# USB_Connector.net
KiCad netlist of a schematic drawn in Altium Designer
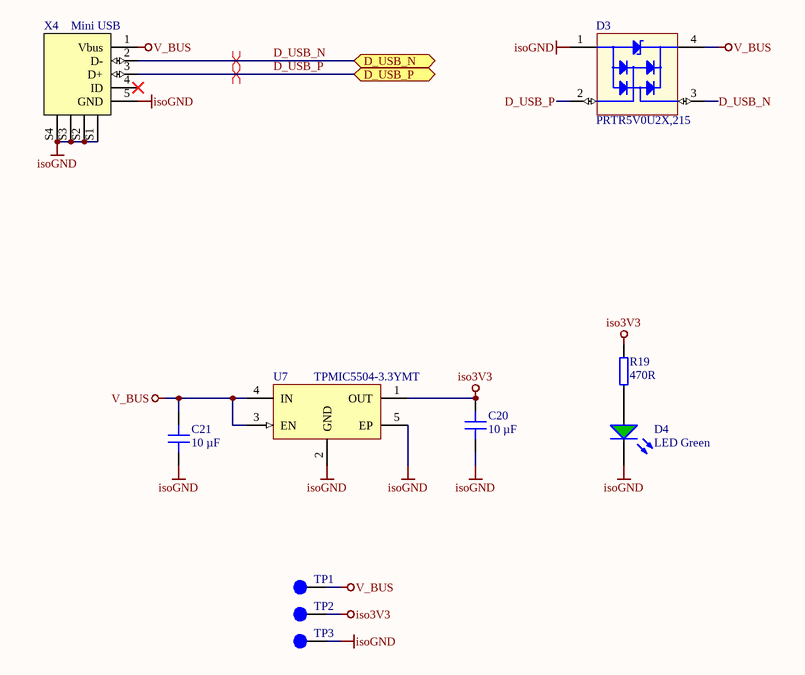
[diagram p0: USB_Connector.SchDoc]

(export (version "E")
  (design (tool "Eeschema 10.0.6"))
  (components
    (comp (ref "C20")
      (value "10 µF")
      (footprint "C_0603")
      (description "Capacitor 0603, 16 VDC, 10 µF, X5R")
      (fields
        (field (name "MANUFACTURER PART NUMBER") "CL10A106MO8NQNC")
        (field (name "MANUFACTURER") "Samsung Electro-Mechanics")
        (field (name "CREATED FROM") "AGeiger")
      )
      (libsource (lib "user") (part "Capacitor"))
    )
    (comp (ref "C21")
      (value "10 µF")
      (footprint "C_0603")
      (description "Capacitor 0603, 16 VDC, 10 µF, X5R")
      (fields
        (field (name "MANUFACTURER PART NUMBER") "CL10A106MO8NQNC")
        (field (name "MANUFACTURER") "Samsung Electro-Mechanics")
        (field (name "CREATED FROM") "AGeiger")
      )
      (libsource (lib "user") (part "Capacitor"))
    )
    (comp (ref "D3")
      (value "PRTR5V0U2X,215")
      (footprint "SOT-143B-4")
      (description "ESD Suppressors / TVS Diodes PRTR5V0U2X/SOT143/SOT4")
      (fields
        (field (name "MANUFACTURER") "Nexperia")
        (field (name "LCSC PART NUMBER") "C12333")
        (field (name "CREATED FROM") "AGeiger")
      )
      (libsource (lib "user") (part "CD143A-SRxx"))
    )
    (comp (ref "D4")
      (value "LED Green")
      (footprint "WL-SMCW_0603")
      (description "LED GREEN 520~535NM 112~258MCD@20MA TOP VIEW 0603 ROHS")
      (fields
        (field (name "MANUFACTURER PART NUMBER") "19-217/GHC-YR1S2/3T")
        (field (name "MANUFACTURER") "Everlight Elec")
        (field (name "CREATED FROM") "T. Wendt")
      )
      (libsource (lib "user") (part "LED_Green"))
    )
    (comp (ref "R19")
      (value "470R")
      (footprint "RES 0603_1608")
      (description "SMD resistor E24 series")
      (fields
        (field (name "MANUFACTURER PART NUMBER") "RK73B1JTTD471J")
        (field (name "MANUFACTURER") "KOA Speer")
        (field (name "CREATED FROM") "MGremer")
      )
      (libsource (lib "user") (part "Resistor"))
    )
    (comp (ref "TP1")
      (value "Testpoint 1mm")
      (footprint "TP_1mm")
      (fields
        (field (name "MANUFACTURER PART NUMBER") "NULL")
        (field (name "CREATED") "2018_06_25_AGeiger")
        (field (name "CREATED FROM") "AGeiger")
      )
      (libsource (lib "user") (part "TP_1mm"))
    )
    (comp (ref "TP2")
      (value "Testpoint 1mm")
      (footprint "TP_1mm")
      (fields
        (field (name "MANUFACTURER PART NUMBER") "NULL")
        (field (name "CREATED") "2018_06_25_AGeiger")
        (field (name "CREATED FROM") "AGeiger")
      )
      (libsource (lib "user") (part "TP_1mm"))
    )
    (comp (ref "TP3")
      (value "Testpoint 1mm")
      (footprint "TP_1mm")
      (fields
        (field (name "MANUFACTURER PART NUMBER") "NULL")
        (field (name "CREATED") "2018_06_25_AGeiger")
        (field (name "CREATED FROM") "AGeiger")
      )
      (libsource (lib "user") (part "TP_1mm"))
    )
    (comp (ref "U7")
      (value "TPMIC5504-3.3YMT")
      (footprint "DFN-4-EP")
      (description "DFN-4-EP(1x1) Linear Voltage Regulators (LDO) ROHS")
      (fields
        (field (name "MANUFACTURER") "TECH PUBLIC")
        (field (name "LCSC PART NUMBER") "C3021135")
        (field (name "CREATED FROM") "AGeiger")
      )
      (libsource (lib "user") (part "TPMIC5504-3.3YMT"))
    )
    (comp (ref "X4")
      (value "Mini USB")
      (footprint "MINI_USB_5S_B _TYPE")
      (description "1A 1 Surface Mount 5P Female -30℃~+80℃ SMD USB Connectors ROHS")
      (fields
        (field (name "MANUFACTURER PART NUMBER") "MINI 5PTP")
        (field (name "MANUFACTURER") "SHOU HAN")
        (field (name "CREATED FROM") "AGeiger")
      )
      (libsource (lib "user") (part "Mini_USB"))
    )
  )
  (nets
    (net (code "1") (name "/D_USB_N") (class "Default")
      (node (ref "D3") (pin "3") (pinfunction "I/O_3") (pintype "bidirectional"))
      (node (ref "X4") (pin "2") (pinfunction "D-_2") (pintype "bidirectional"))
    )
    (net (code "2") (name "/D_USB_P") (class "Default")
      (node (ref "D3") (pin "2") (pinfunction "I/O_2") (pintype "bidirectional"))
      (node (ref "X4") (pin "3") (pinfunction "D+_3") (pintype "bidirectional"))
    )
    (net (code "3") (name "Net-(D4-A)") (class "Default")
      (node (ref "D4") (pin "2") (pinfunction "A_2") (pintype "passive"))
      (node (ref "R19") (pin "1") (pinfunction "1_1") (pintype "passive"))
    )
    (net (code "4") (name "V_BUS") (class "Default")
      (node (ref "C21") (pin "2") (pinfunction "2_2") (pintype "passive"))
      (node (ref "D3") (pin "4") (pinfunction "REF_4") (pintype "passive"))
      (node (ref "TP1") (pin "1") (pintype "passive"))
      (node (ref "U7") (pin "3") (pinfunction "EN_3") (pintype "input"))
      (node (ref "U7") (pin "4") (pinfunction "IN_4") (pintype "power_in"))
      (node (ref "X4") (pin "1") (pinfunction "Vbus_1") (pintype "power_in"))
    )
    (net (code "5") (name "iso3V3") (class "Default")
      (node (ref "C20") (pin "2") (pinfunction "2_2") (pintype "passive"))
      (node (ref "R19") (pin "2") (pinfunction "2_2") (pintype "passive"))
      (node (ref "TP2") (pin "1") (pintype "passive"))
      (node (ref "U7") (pin "1") (pinfunction "OUT_1") (pintype "power_in"))
    )
    (net (code "6") (name "isoGND") (class "Default")
      (node (ref "C20") (pin "1") (pinfunction "1_1") (pintype "passive"))
      (node (ref "C21") (pin "1") (pinfunction "1_1") (pintype "passive"))
      (node (ref "D3") (pin "1") (pinfunction "GND_1") (pintype "passive"))
      (node (ref "D4") (pin "1") (pinfunction "K_1") (pintype "passive"))
      (node (ref "TP3") (pin "1") (pintype "passive"))
      (node (ref "U7") (pin "2") (pinfunction "GND_2") (pintype "power_in"))
      (node (ref "U7") (pin "5") (pinfunction "EP_5") (pintype "power_in"))
      (node (ref "X4") (pin "5") (pinfunction "GND_5") (pintype "power_in"))
      (node (ref "X4") (pin "S1") (pinfunction "S1_S1") (pintype "passive"))
      (node (ref "X4") (pin "S2") (pinfunction "S2_S2") (pintype "passive"))
      (node (ref "X4") (pin "S3") (pinfunction "S3_S3") (pintype "passive"))
      (node (ref "X4") (pin "S4") (pinfunction "S4_S4") (pintype "passive"))
    )
    (net (code "7") (name "unconnected-(X4-ID-Pad4)") (class "Default")
      (node (ref "X4") (pin "4") (pinfunction "ID_4") (pintype "passive+no_connect"))
    )
  )
)
